# tinybridge-ftdi.net
KiCad netlist of a schematic drawn in EAGLE
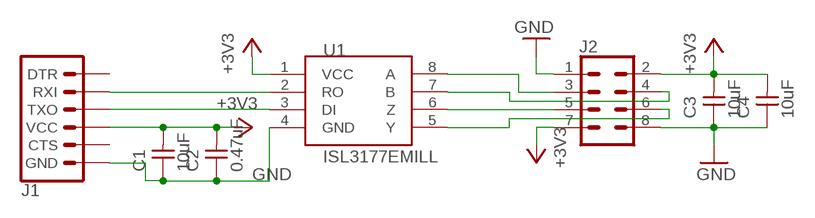
[diagram p0: schematic, sheet 1]

(export (version "E")
  (design (tool "Eeschema 10.0.6"))
  (components
    (comp (ref "C1")
      (value "10uF")
      (footprint "eagle-import:C1206")
      (libsource (lib "eagle-import") (part "CAP-UNPOLARIZED"))
    )
    (comp (ref "C2")
      (value "0.47uF")
      (footprint "eagle-import:C1206")
      (libsource (lib "eagle-import") (part "CAP-UNPOLARIZED"))
    )
    (comp (ref "C3")
      (value "10uF")
      (footprint "eagle-import:C1206")
      (libsource (lib "eagle-import") (part "CAP-UNPOLARIZED"))
    )
    (comp (ref "C4")
      (value "10uF")
      (footprint "eagle-import:C1206")
      (libsource (lib "eagle-import") (part "CAP-UNPOLARIZED"))
    )
    (comp (ref "J1")
      (value "6_PIN_SERIAL_TARGETMILLING")
      (footprint "eagle-import:1X06-SQUISH")
      (libsource (lib "eagle-import") (part "6_PIN_SERIAL_TARGETMILLING"))
    )
    (comp (ref "J2")
      (value "CONN_04X2SHROUDED-SQUISH")
      (footprint "eagle-import:2X4-SHROUDED-SQUISH")
      (libsource (lib "eagle-import") (part "CONN_04X2SHROUDED-SQUISH"))
    )
    (comp (ref "U1")
      (value "ISL3177EMILL")
      (footprint "eagle-import:MSOP8-8MILPADS")
      (libsource (lib "eagle-import") (part "ISL3177EMILL"))
    )
  )
  (nets
    (net (code "1") (name "+3V3") (class "Default")
      (node (ref "C1") (pin "2") (pinfunction "2_2") (pintype "passive"))
      (node (ref "C2") (pin "2") (pinfunction "2_2") (pintype "passive"))
      (node (ref "C3") (pin "2") (pinfunction "2_2") (pintype "passive"))
      (node (ref "C4") (pin "2") (pinfunction "2_2") (pintype "passive"))
      (node (ref "J1") (pin "4") (pinfunction "VCC_4") (pintype "passive"))
      (node (ref "J2") (pin "2") (pinfunction "2_2") (pintype "passive"))
      (node (ref "J2") (pin "7") (pinfunction "7_7") (pintype "passive"))
      (node (ref "U1") (pin "1") (pinfunction "VCC_1") (pintype "bidirectional"))
    )
    (net (code "2") (name "GND") (class "Default")
      (node (ref "C1") (pin "1") (pinfunction "1_1") (pintype "passive"))
      (node (ref "C2") (pin "1") (pinfunction "1_1") (pintype "passive"))
      (node (ref "C3") (pin "1") (pinfunction "1_1") (pintype "passive"))
      (node (ref "C4") (pin "1") (pinfunction "1_1") (pintype "passive"))
      (node (ref "J1") (pin "6") (pinfunction "GND_6") (pintype "passive"))
      (node (ref "J2") (pin "1") (pinfunction "1_1") (pintype "passive"))
      (node (ref "J2") (pin "8") (pinfunction "8_8") (pintype "passive"))
      (node (ref "U1") (pin "4") (pinfunction "GND_4") (pintype "bidirectional"))
    )
    (net (code "3") (name "Net-(J1-RXI)") (class "Default")
      (node (ref "J1") (pin "2") (pinfunction "RXI_2") (pintype "passive"))
      (node (ref "U1") (pin "2") (pinfunction "RO_2") (pintype "bidirectional"))
    )
    (net (code "4") (name "Net-(J1-TXO)") (class "Default")
      (node (ref "J1") (pin "3") (pinfunction "TXO_3") (pintype "passive"))
      (node (ref "U1") (pin "3") (pinfunction "DI_3") (pintype "bidirectional"))
    )
    (net (code "5") (name "Net-(U1-A)") (class "Default")
      (node (ref "J2") (pin "3") (pinfunction "3_3") (pintype "passive"))
      (node (ref "U1") (pin "8") (pinfunction "A_8") (pintype "bidirectional"))
    )
    (net (code "6") (name "Net-(U1-B)") (class "Default")
      (node (ref "J2") (pin "4") (pinfunction "4_4") (pintype "passive"))
      (node (ref "U1") (pin "7") (pinfunction "B_7") (pintype "bidirectional"))
    )
    (net (code "7") (name "Net-(U1-Y)") (class "Default")
      (node (ref "J2") (pin "6") (pinfunction "6_6") (pintype "passive"))
      (node (ref "U1") (pin "5") (pinfunction "Y_5") (pintype "bidirectional"))
    )
    (net (code "8") (name "Net-(U1-Z)") (class "Default")
      (node (ref "J2") (pin "5") (pinfunction "5_5") (pintype "passive"))
      (node (ref "U1") (pin "6") (pinfunction "Z_6") (pintype "bidirectional"))
    )
    (net (code "9") (name "unconnected-(J1-CTS-Pad5)") (class "Default")
      (node (ref "J1") (pin "5") (pinfunction "CTS_5") (pintype "passive"))
    )
    (net (code "10") (name "unconnected-(J1-DTR-Pad1)") (class "Default")
      (node (ref "J1") (pin "1") (pinfunction "DTR_1") (pintype "passive"))
    )
  )
)
